# Controller_Sheet.net
KiCad netlist of a schematic drawn in Altium Designer
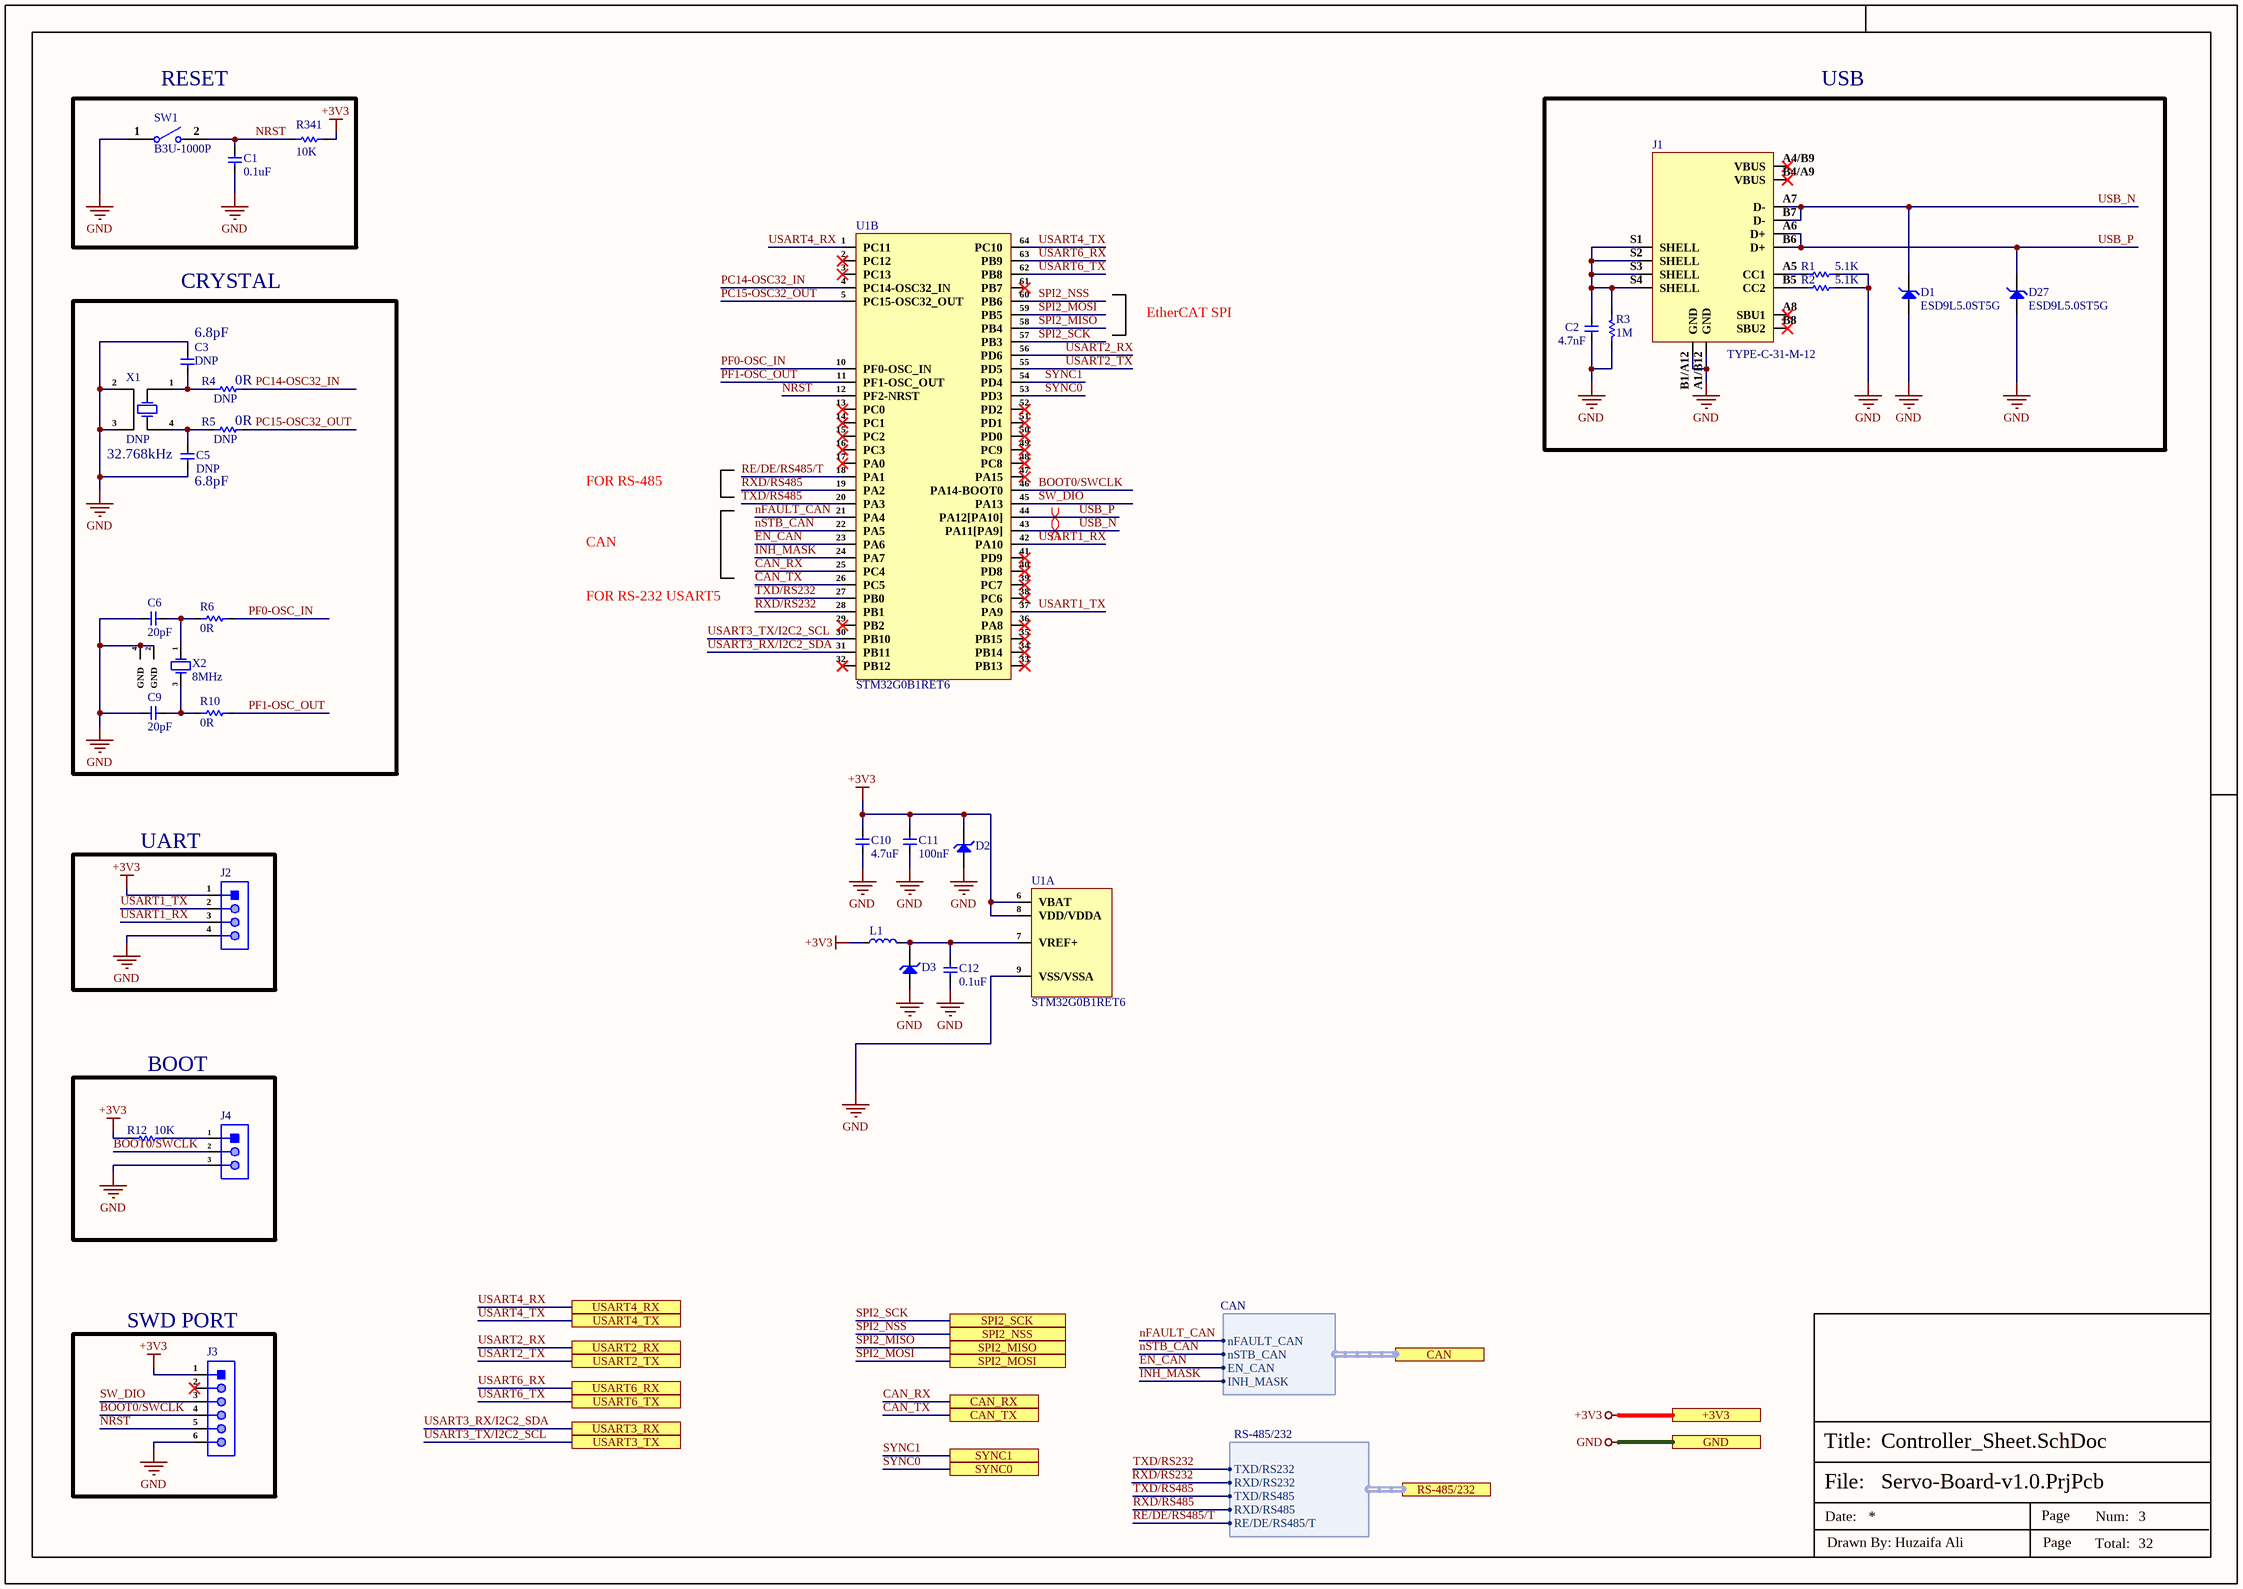
[diagram p0: Controller_Sheet.SchDoc]

(export (version "E")
  (design (tool "Eeschema 10.0.6"))
  (components
    (comp (ref "C1")
      (value "0.1uF")
      (footprint "Cap-0402")
      (description "CAP CER 0.1UF 16V X7R 0402")
      (fields
        (field (name "MANUFACTURER") "Yageo")
        (field (name "MANUFACTURER PART NUMBER") "CC0402JRX7R7BB104")
      )
      (libsource (lib "eSpark Libraries") (part "CC0402JRX7R7BB104"))
    )
    (comp (ref "C2")
      (value "4.7nF")
      (footprint "Cap-0603")
      (description "CAP CER 4700PF 50V C0G/NPO 0603")
      (fields
        (field (name "MANUFACTURER") "Yageo")
        (field (name "MANUFACTURER PART NUMBER") "CC0603JRNPO9BN472")
      )
      (libsource (lib "eSpark_centralized_Library(2022)") (part "CC0603JRNPO9BN472"))
    )
    (comp (ref "C3")
      (value "DNP")
      (footprint "Cap-0402")
      (description "CAP CER 6.8PF 50V C0G/NPO 0402")
      (fields
        (field (name "MANUFACTURER") "Yageo")
        (field (name "MANUFACTURER PART NUMBER") "CC0402CRNPO9BN6R8")
      )
      (libsource (lib "eSpark Libraries") (part "CC0402CRNPO9BN6R8"))
    )
    (comp (ref "C5")
      (value "DNP")
      (footprint "Cap-0402")
      (description "CAP CER 6.8PF 50V C0G/NPO 0402")
      (fields
        (field (name "MANUFACTURER") "Yageo")
        (field (name "MANUFACTURER PART NUMBER") "CC0402CRNPO9BN6R8")
      )
      (libsource (lib "eSpark Libraries") (part "CC0402CRNPO9BN6R8"))
    )
    (comp (ref "C6")
      (value "20pF")
      (footprint "Cap-0402")
      (description "CAP CER 20PF 50V C0G/NPO 0402")
      (fields (field (name "LCSC PART NUMBER") "C107000") (field (name "MANUFACTURER") "Yageo"))
      (libsource (lib "eSpark Libraries") (part "CC0402JRNPO9BN200"))
    )
    (comp (ref "C9")
      (value "20pF")
      (footprint "Cap-0402")
      (description "CAP CER 20PF 50V C0G/NPO 0402")
      (fields (field (name "LCSC PART NUMBER") "C107000") (field (name "MANUFACTURER") "Yageo"))
      (libsource (lib "eSpark Libraries") (part "CC0402JRNPO9BN200"))
    )
    (comp (ref "C10")
      (value "4.7uF")
      (footprint "Cap-0402")
      (description "CAP CER 4.7UF 10V X5R 0402")
      (fields
        (field (name "MANUFACTURER") "Yageo")
        (field (name "MANUFACTURER PART NUMBER") "CC0402KRX5R6BB475")
      )
      (libsource (lib "eSpark Libraries") (part "CC0402KRX5R6BB475"))
    )
    (comp (ref "C11")
      (value "100nF")
      (footprint "cap-0402")
      (description "CAP CER 0.1UF 50V X7R 0402")
      (fields
        (field (name "MANUFACTURER") "TDK")
        (field (name "MANUFACTURER PART NUMBER") "C1005X7R1H104KT000F")
      )
      (libsource (lib "eSpark Libraries") (part "C1005X7R1H104KT000F"))
    )
    (comp (ref "C12")
      (value "0.1uF")
      (footprint "Cap-0402")
      (description "CAP CER 0.1UF 16V X7R 0402")
      (fields
        (field (name "MANUFACTURER") "Yageo")
        (field (name "MANUFACTURER PART NUMBER") "CC0402JRX7R7BB104")
      )
      (libsource (lib "eSpark Libraries") (part "CC0402JRX7R7BB104"))
    )
    (comp (ref "D1")
      (value "ESD9L5.0ST5G")
      (footprint "SOD-923.")
      (description "TVS DIODE 5V 9.8V SOD923")
      (fields (field (name "MANUFACTURER") "ON Semiconductor") (field (name "LCSC PART NUMBER") "C82326"))
      (libsource (lib "eSpark Libraries") (part "ESD9L5.0ST5G"))
    )
    (comp (ref "D2")
      (value "AZ3003-01G")
      (footprint "SOD-123")
      (description "TVS SURGE PROTECTOR 1-CH 3.3V")
      (fields (field (name "MANUFACTURER") "Amazing"))
      (libsource (lib "eSpark Libraries") (part "AZ3003-01G"))
    )
    (comp (ref "D3")
      (value "AZ3003-01G")
      (footprint "SOD-123")
      (description "TVS SURGE PROTECTOR 1-CH 3.3V")
      (fields (field (name "MANUFACTURER") "Amazing"))
      (libsource (lib "eSpark Libraries") (part "AZ3003-01G"))
    )
    (comp (ref "D27")
      (value "ESD9L5.0ST5G")
      (footprint "SOD-923.")
      (description "TVS DIODE 5V 9.8V SOD923")
      (fields (field (name "MANUFACTURER") "ON Semiconductor") (field (name "LCSC PART NUMBER") "C82326"))
      (libsource (lib "eSpark Libraries") (part "ESD9L5.0ST5G"))
    )
    (comp (ref "J1")
      (value "TYPE-C-31-M-12")
      (footprint "TYPE-C-31-M-12_")
      (description "5A 1 16P Female Type-C SMD USB Connectors ROHS")
      (fields
        (field (name "MANUFACTURER") "Korean Hroparts Elec")
        (field (name "LCSC PART NUMBER") "C165948")
      )
      (libsource (lib "eSpark Libraries") (part "TYPE-C-31-M-12"))
    )
    (comp (ref "J2")
      (value "X6511WV-04H-C60D30")
      (footprint "HDR1X4_")
      (fields (field (name "MANUFACTURER") "XKB") (field (name "LCSC PART NUMBER") "C706876"))
      (libsource (lib "eSpark Libraries") (part "X6511WV-04H-C60D30"))
    )
    (comp (ref "J3")
      (value "X6511WV-06H-C60D30")
      (footprint "HDR1X6_")
      (fields (field (name "MANUFACTURER") "XKB") (field (name "LCSC PART NUMBER") "C706878"))
      (libsource (lib "eSpark Libraries") (part "X6511WV-06H-C60D30"))
    )
    (comp (ref "J4")
      (value "68000-103HLF")
      (footprint "HDR1X3_")
      (description "CONN HEADER VERT 3POS 2.54MM")
      (fields (field (name "LCSC PART NUMBER") "C168677"))
      (libsource (lib "eSpark Libraries") (part "68000-103HLF"))
    )
    (comp (ref "L1")
      (value "BLM15AG601SN1D")
      (footprint "IND-0402")
      (description "FERRITE BEAD 600 OHM 0402 1LN")
      (fields (field (name "MANUFACTURER") "Murata") (field (name "TOLERANCE") "25%"))
      (libsource (lib "eSpark Libraries") (part "BLM15AG601SN1D"))
    )
    (comp (ref "R1")
      (value "5.1K")
      (footprint "Res-0402")
      (description "RES 5.1K OHM 1% 1/16W 0402")
      (fields
        (field (name "MANUFACTURER") "Yageo")
        (field (name "MANUFACTURER PART NUMBER") "RC0402FR-075K1L")
      )
      (libsource (lib "eSpark Libraries") (part "RC0402FR-075K1L"))
    )
    (comp (ref "R2")
      (value "5.1K")
      (footprint "Res-0402")
      (description "RES 5.1K OHM 1% 1/16W 0402")
      (fields
        (field (name "MANUFACTURER") "Yageo")
        (field (name "MANUFACTURER PART NUMBER") "RC0402FR-075K1L")
      )
      (libsource (lib "eSpark Libraries") (part "RC0402FR-075K1L"))
    )
    (comp (ref "R3")
      (value "1M")
      (footprint "Res-0402")
      (description "RES SMD 1M OHM 5% 1/16W 0402")
      (fields
        (field (name "MANUFACTURER") "Yageo")
        (field (name "MANUFACTURER PART NUMBER") "AF0402JR-071ML")
      )
      (libsource (lib "eSpark_centralized_Library(2022)") (part "AF0402JR-071ML"))
    )
    (comp (ref "R4")
      (value "DNP")
      (footprint "Res-0603")
      (description "RES 0 OHM JUMPER 1/10W 0603")
      (fields
        (field (name "MANUFACTURER") "Yageo")
        (field (name "MANUFACTURER PART NUMBER") "RC0603JR-070RL")
      )
      (libsource (lib "eSpark Libraries") (part "RC0603JR-070RL"))
    )
    (comp (ref "R5")
      (value "DNP")
      (footprint "Res-0603")
      (description "RES 0 OHM JUMPER 1/10W 0603")
      (fields
        (field (name "MANUFACTURER") "Yageo")
        (field (name "MANUFACTURER PART NUMBER") "RC0603JR-070RL")
      )
      (libsource (lib "eSpark Libraries") (part "RC0603JR-070RL"))
    )
    (comp (ref "R6")
      (value "0R")
      (footprint "Res-0603")
      (description "RES 0 OHM JUMPER 1/10W 0603")
      (fields
        (field (name "MANUFACTURER") "Yageo")
        (field (name "MANUFACTURER PART NUMBER") "RC0603JR-070RL")
      )
      (libsource (lib "eSpark Libraries") (part "RC0603JR-070RL"))
    )
    (comp (ref "R10")
      (value "0R")
      (footprint "Res-0603")
      (description "RES 0 OHM JUMPER 1/10W 0603")
      (fields
        (field (name "MANUFACTURER") "Yageo")
        (field (name "MANUFACTURER PART NUMBER") "RC0603JR-070RL")
      )
      (libsource (lib "eSpark Libraries") (part "RC0603JR-070RL"))
    )
    (comp (ref "R12")
      (value "10K")
      (footprint "Res-0402")
      (description "RES 10K OHM 1% 1/16W 0402")
      (fields
        (field (name "MANUFACTURER") "Yageo")
        (field (name "MANUFACTURER PART NUMBER") "RC0402FR-0710KL")
      )
      (libsource (lib "eSpark Libraries") (part "RC0402FR-0710KL"))
    )
    (comp (ref "R341")
      (value "10K")
      (footprint "Res-0402")
      (description "RES 10K OHM 1% 1/16W 0402")
      (fields
        (field (name "MANUFACTURER") "Yageo")
        (field (name "MANUFACTURER PART NUMBER") "RC0402FR-0710KL")
      )
      (libsource (lib "eSpark Libraries") (part "RC0402FR-0710KL"))
    )
    (comp (ref "SW1")
      (value "B3U-1000P")
      (footprint "B3U-1000P")
      (description "SWITCH TACTILE SPST-NO 0.05A 12V")
      (fields (field (name "MANUFACTURER") "Omron") (field (name "LCSC PART NUMBER") "C231329"))
      (libsource (lib "eSpark Libraries") (part "B3U-1000P"))
    )
    (comp (ref "U1")
      (value "STM32G0B1RET6")
      (footprint "LQFP-64(10x10)")
      (description "IC MCU 32BIT 512KB FLASH 64LQFP")
      (fields (field (name "MANUFACTURER") "STMicroelectronics") (field (name "LCSC PART NUMBER") "C2829307"))
      (libsource (lib "eSpark Libraries") (part "STM32G0B1RET6"))
    )
    (comp (ref "X1")
      (value "DNP")
      (footprint "MC-306")
      (description "32.768kHz 12.5pF ±20ppm MC-306 Crystals ROHS")
      (fields
        (field (name "MANUFACTURER") "Seiko Epson")
        (field (name "MANUFACTURER PART NUMBER") "MC-306 32.7680K-A0:ROHS")
      )
      (libsource (lib "eSpark Libraries") (part "MC-306 32.7680K-A0{colon}ROHS"))
    )
    (comp (ref "X2")
      (value "8MHz")
      (footprint "5TJ480000XYLBC_")
      (description "8MHz 18pF ±10ppm SMD5032-4P Crystals ROHS")
      (fields (field (name "MANUFACTURER") "JYJE") (field (name "MANUFACTURER PART NUMBER") "5TJ480000XYLBC"))
      (libsource (lib "eSpark Libraries") (part "5TJ480000XYLBC"))
    )
  )
  (nets
    (net (code "3") (name "+3V3") (class "Default")
      (node (ref "C10") (pin "2") (pinfunction "2_2") (pintype "passive"))
      (node (ref "C11") (pin "2") (pinfunction "2_2") (pintype "passive"))
      (node (ref "D2") (pin "2") (pinfunction "K_2") (pintype "passive"))
      (node (ref "J2") (pin "1") (pinfunction "1_1") (pintype "passive"))
      (node (ref "J3") (pin "1") (pinfunction "1_1") (pintype "passive"))
      (node (ref "L1") (pin "1") (pinfunction "1_1") (pintype "passive"))
      (node (ref "R12") (pin "2") (pinfunction "2_2") (pintype "passive"))
      (node (ref "R341") (pin "2") (pinfunction "2_2") (pintype "passive"))
      (node (ref "U1") (pin "6") (pinfunction "VBAT_6") (pintype "passive"))
      (node (ref "U1") (pin "8") (pinfunction "VDD/VDDA_8") (pintype "passive"))
    )
    (net (code "4") (name "/BOOT0{slash}SWCLK") (class "Default")
      (node (ref "J3") (pin "4") (pinfunction "4_4") (pintype "passive"))
      (node (ref "J4") (pin "2") (pinfunction "2_2") (pintype "passive"))
      (node (ref "U1") (pin "46") (pinfunction "PA14-BOOT0_46") (pintype "passive"))
    )
    (net (code "5") (name "/CAN_RX") (class "Default")
      (node (ref "U1") (pin "25") (pinfunction "PC4_25") (pintype "passive"))
    )
    (net (code "6") (name "/CAN_TX") (class "Default")
      (node (ref "U1") (pin "26") (pinfunction "PC5_26") (pintype "passive"))
    )
    (net (code "7") (name "/EN_CAN") (class "Default")
      (node (ref "U1") (pin "23") (pinfunction "PA6_23") (pintype "passive"))
    )
    (net (code "8") (name "/INH_MASK") (class "Default")
      (node (ref "U1") (pin "24") (pinfunction "PA7_24") (pintype "passive"))
    )
    (net (code "9") (name "/NRST") (class "Default")
      (node (ref "C1") (pin "2") (pinfunction "2_2") (pintype "passive"))
      (node (ref "J3") (pin "5") (pinfunction "5_5") (pintype "passive"))
      (node (ref "R341") (pin "1") (pinfunction "1_1") (pintype "passive"))
      (node (ref "SW1") (pin "2") (pinfunction "2_2") (pintype "passive"))
      (node (ref "U1") (pin "12") (pinfunction "PF2-NRST_12") (pintype "passive"))
    )
    (net (code "10") (name "/PC14-OSC32_IN") (class "Default")
      (node (ref "R4") (pin "2") (pinfunction "2_2") (pintype "passive"))
      (node (ref "U1") (pin "4") (pinfunction "PC14-OSC32_IN_4") (pintype "passive"))
    )
    (net (code "11") (name "/PC15-OSC32_OUT") (class "Default")
      (node (ref "R5") (pin "2") (pinfunction "2_2") (pintype "passive"))
      (node (ref "U1") (pin "5") (pinfunction "PC15-OSC32_OUT_5") (pintype "passive"))
    )
    (net (code "12") (name "/PF0-OSC_IN") (class "Default")
      (node (ref "R6") (pin "2") (pinfunction "2_2") (pintype "passive"))
      (node (ref "U1") (pin "10") (pinfunction "PF0-OSC_IN_10") (pintype "passive"))
    )
    (net (code "13") (name "/PF1-OSC_OUT") (class "Default")
      (node (ref "R10") (pin "2") (pinfunction "2_2") (pintype "passive"))
      (node (ref "U1") (pin "11") (pinfunction "PF1-OSC_OUT_11") (pintype "passive"))
    )
    (net (code "14") (name "/RE{slash}DE{slash}RS485{slash}T") (class "Default")
      (node (ref "U1") (pin "18") (pinfunction "PA1_18") (pintype "passive"))
    )
    (net (code "15") (name "/RXD{slash}RS232") (class "Default")
      (node (ref "U1") (pin "28") (pinfunction "PB1_28") (pintype "passive"))
    )
    (net (code "16") (name "/RXD{slash}RS485") (class "Default")
      (node (ref "U1") (pin "19") (pinfunction "PA2_19") (pintype "passive"))
    )
    (net (code "17") (name "/SPI2_MISO") (class "Default")
      (node (ref "U1") (pin "58") (pinfunction "PB4_58") (pintype "passive"))
    )
    (net (code "18") (name "/SPI2_MOSI") (class "Default")
      (node (ref "U1") (pin "59") (pinfunction "PB5_59") (pintype "passive"))
    )
    (net (code "19") (name "/SPI2_NSS") (class "Default")
      (node (ref "U1") (pin "60") (pinfunction "PB6_60") (pintype "passive"))
    )
    (net (code "20") (name "/SPI2_SCK") (class "Default")
      (node (ref "U1") (pin "57") (pinfunction "PB3_57") (pintype "passive"))
    )
    (net (code "21") (name "/SW_DIO") (class "Default")
      (node (ref "J3") (pin "3") (pinfunction "3_3") (pintype "passive"))
      (node (ref "U1") (pin "45") (pinfunction "PA13_45") (pintype "passive"))
    )
    (net (code "22") (name "/SYNC0") (class "Default")
      (node (ref "U1") (pin "53") (pinfunction "PD3_53") (pintype "passive"))
    )
    (net (code "23") (name "/SYNC1") (class "Default")
      (node (ref "U1") (pin "54") (pinfunction "PD4_54") (pintype "passive"))
    )
    (net (code "24") (name "/TXD{slash}RS232") (class "Default")
      (node (ref "U1") (pin "27") (pinfunction "PB0_27") (pintype "passive"))
    )
    (net (code "25") (name "/TXD{slash}RS485") (class "Default")
      (node (ref "U1") (pin "20") (pinfunction "PA3_20") (pintype "passive"))
    )
    (net (code "26") (name "/USART1_RX") (class "Default")
      (node (ref "J2") (pin "3") (pinfunction "3_3") (pintype "passive"))
      (node (ref "U1") (pin "42") (pinfunction "PA10_42") (pintype "passive"))
    )
    (net (code "27") (name "/USART1_TX") (class "Default")
      (node (ref "J2") (pin "2") (pinfunction "2_2") (pintype "passive"))
      (node (ref "U1") (pin "37") (pinfunction "PA9_37") (pintype "passive"))
    )
    (net (code "28") (name "/USART2_RX") (class "Default")
      (node (ref "U1") (pin "56") (pinfunction "PD6_56") (pintype "passive"))
    )
    (net (code "29") (name "/USART2_TX") (class "Default")
      (node (ref "U1") (pin "55") (pinfunction "PD5_55") (pintype "passive"))
    )
    (net (code "30") (name "/USART3_RX{slash}I2C2_SDA") (class "Default")
      (node (ref "U1") (pin "31") (pinfunction "PB11_31") (pintype "passive"))
    )
    (net (code "31") (name "/USART3_TX{slash}I2C2_SCL") (class "Default")
      (node (ref "U1") (pin "30") (pinfunction "PB10_30") (pintype "passive"))
    )
    (net (code "32") (name "/USART4_RX") (class "Default")
      (node (ref "U1") (pin "1") (pinfunction "PC11_1") (pintype "passive"))
    )
    (net (code "33") (name "/USART4_TX") (class "Default")
      (node (ref "U1") (pin "64") (pinfunction "PC10_64") (pintype "passive"))
    )
    (net (code "34") (name "/USART6_RX") (class "Default")
      (node (ref "U1") (pin "63") (pinfunction "PB9_63") (pintype "passive"))
    )
    (net (code "35") (name "/USART6_TX") (class "Default")
      (node (ref "U1") (pin "62") (pinfunction "PB8_62") (pintype "passive"))
    )
    (net (code "36") (name "/USB_N") (class "Default")
      (node (ref "D1") (pin "1") (pinfunction "K_1") (pintype "passive"))
      (node (ref "J1") (pin "A7") (pinfunction "D-_A7") (pintype "passive"))
      (node (ref "J1") (pin "B7") (pinfunction "D-_B7") (pintype "passive"))
      (node (ref "U1") (pin "43") (pinfunction "PA11[PA9]_43") (pintype "passive"))
    )
    (net (code "37") (name "/USB_P") (class "Default")
      (node (ref "D27") (pin "1") (pinfunction "K_1") (pintype "passive"))
      (node (ref "J1") (pin "A6") (pinfunction "D+_A6") (pintype "passive"))
      (node (ref "J1") (pin "B6") (pinfunction "D+_B6") (pintype "passive"))
      (node (ref "U1") (pin "44") (pinfunction "PA12[PA10]_44") (pintype "passive"))
    )
    (net (code "38") (name "/nFAULT_CAN") (class "Default")
      (node (ref "U1") (pin "21") (pinfunction "PA4_21") (pintype "passive"))
    )
    (net (code "39") (name "/nSTB_CAN") (class "Default")
      (node (ref "U1") (pin "22") (pinfunction "PA5_22") (pintype "passive"))
    )
    (net (code "42") (name "GND") (class "Default")
      (node (ref "C1") (pin "1") (pinfunction "1_1") (pintype "passive"))
      (node (ref "C10") (pin "1") (pinfunction "1_1") (pintype "passive"))
      (node (ref "C11") (pin "1") (pinfunction "1_1") (pintype "passive"))
      (node (ref "C12") (pin "1") (pinfunction "1_1") (pintype "passive"))
      (node (ref "C2") (pin "1") (pinfunction "1_1") (pintype "passive"))
      (node (ref "C3") (pin "1") (pinfunction "1_1") (pintype "passive"))
      (node (ref "C5") (pin "2") (pinfunction "2_2") (pintype "passive"))
      (node (ref "C6") (pin "1") (pinfunction "1_1") (pintype "passive"))
      (node (ref "C9") (pin "1") (pinfunction "1_1") (pintype "passive"))
      (node (ref "D1") (pin "2") (pinfunction "A_2") (pintype "passive"))
      (node (ref "D2") (pin "1") (pinfunction "A_1") (pintype "passive"))
      (node (ref "D27") (pin "2") (pinfunction "A_2") (pintype "passive"))
      (node (ref "D3") (pin "1") (pinfunction "A_1") (pintype "passive"))
      (node (ref "J1") (pin "A1/B12") (pinfunction "GND_A1/B12") (pintype "power_in"))
      (node (ref "J1") (pin "B1/A12") (pinfunction "GND_B1/A12") (pintype "power_in"))
      (node (ref "J2") (pin "4") (pinfunction "4_4") (pintype "passive"))
      (node (ref "J3") (pin "6") (pinfunction "6_6") (pintype "passive"))
      (node (ref "J4") (pin "3") (pinfunction "3_3") (pintype "passive"))
      (node (ref "R1") (pin "2") (pinfunction "2_2") (pintype "passive"))
      (node (ref "R2") (pin "2") (pinfunction "2_2") (pintype "passive"))
      (node (ref "R3") (pin "2") (pinfunction "2_2") (pintype "passive"))
      (node (ref "SW1") (pin "1") (pinfunction "1_1") (pintype "passive"))
      (node (ref "U1") (pin "9") (pinfunction "VSS/VSSA_9") (pintype "passive"))
      (node (ref "X1") (pin "2") (pinfunction "2_2") (pintype "passive"))
      (node (ref "X1") (pin "3") (pinfunction "3_3") (pintype "passive"))
      (node (ref "X2") (pin "2") (pinfunction "GND_2") (pintype "passive"))
      (node (ref "X2") (pin "4") (pinfunction "GND_4") (pintype "passive"))
    )
    (net (code "43") (name "Net-(C2-Pad2)") (class "Default")
      (node (ref "C2") (pin "2") (pinfunction "2_2") (pintype "passive"))
      (node (ref "J1") (pin "S1") (pinfunction "SHELL_S1") (pintype "passive"))
      (node (ref "J1") (pin "S2") (pinfunction "SHELL_S2") (pintype "passive"))
      (node (ref "J1") (pin "S3") (pinfunction "SHELL_S3") (pintype "passive"))
      (node (ref "J1") (pin "S4") (pinfunction "SHELL_S4") (pintype "passive"))
      (node (ref "R3") (pin "1") (pinfunction "1_1") (pintype "passive"))
    )
    (net (code "44") (name "Net-(D3-K)") (class "Default")
      (node (ref "C12") (pin "2") (pinfunction "2_2") (pintype "passive"))
      (node (ref "D3") (pin "2") (pinfunction "K_2") (pintype "passive"))
      (node (ref "L1") (pin "2") (pinfunction "2_2") (pintype "passive"))
      (node (ref "U1") (pin "7") (pinfunction "VREF+_7") (pintype "passive"))
    )
    (net (code "45") (name "Net-(J1-CC1)") (class "Default")
      (node (ref "J1") (pin "A5") (pinfunction "CC1_A5") (pintype "passive"))
      (node (ref "R1") (pin "1") (pinfunction "1_1") (pintype "passive"))
    )
    (net (code "46") (name "Net-(J1-CC2)") (class "Default")
      (node (ref "J1") (pin "B5") (pinfunction "CC2_B5") (pintype "passive"))
      (node (ref "R2") (pin "1") (pinfunction "1_1") (pintype "passive"))
    )
    (net (code "47") (name "Net-(J4-Pad1)") (class "Default")
      (node (ref "J4") (pin "1") (pinfunction "1_1") (pintype "passive"))
      (node (ref "R12") (pin "1") (pinfunction "1_1") (pintype "passive"))
    )
    (net (code "48") (name "Net-(X1-OSC1)") (class "Default")
      (node (ref "C3") (pin "2") (pinfunction "2_2") (pintype "passive"))
      (node (ref "R4") (pin "1") (pinfunction "1_1") (pintype "passive"))
      (node (ref "X1") (pin "1") (pinfunction "OSC1_1") (pintype "passive"))
    )
    (net (code "49") (name "Net-(X1-OSC2)") (class "Default")
      (node (ref "C5") (pin "1") (pinfunction "1_1") (pintype "passive"))
      (node (ref "R5") (pin "1") (pinfunction "1_1") (pintype "passive"))
      (node (ref "X1") (pin "4") (pinfunction "OSC2_4") (pintype "passive"))
    )
    (net (code "50") (name "Net-(X2-OSC1)") (class "Default")
      (node (ref "C6") (pin "2") (pinfunction "2_2") (pintype "passive"))
      (node (ref "R6") (pin "1") (pinfunction "1_1") (pintype "passive"))
      (node (ref "X2") (pin "1") (pinfunction "OSC1_1") (pintype "passive"))
    )
    (net (code "51") (name "Net-(X2-OSC2)") (class "Default")
      (node (ref "C9") (pin "2") (pinfunction "2_2") (pintype "passive"))
      (node (ref "R10") (pin "1") (pinfunction "1_1") (pintype "passive"))
      (node (ref "X2") (pin "3") (pinfunction "OSC2_3") (pintype "passive"))
    )
    (net (code "52") (name "unconnected-(J1-SBU1-PadA8)") (class "Default")
      (node (ref "J1") (pin "A8") (pinfunction "SBU1_A8") (pintype "passive+no_connect"))
    )
    (net (code "53") (name "unconnected-(J1-SBU2-PadB8)") (class "Default")
      (node (ref "J1") (pin "B8") (pinfunction "SBU2_B8") (pintype "passive+no_connect"))
    )
    (net (code "54") (name "unconnected-(J1-VBUS-PadA4{slash}B9)") (class "Default")
      (node (ref "J1") (pin "A4/B9") (pinfunction "VBUS_A4/B9") (pintype "power_in+no_connect"))
    )
    (net (code "55") (name "unconnected-(J1-VBUS-PadB4{slash}A9)") (class "Default")
      (node (ref "J1") (pin "B4/A9") (pinfunction "VBUS_B4/A9") (pintype "power_in+no_connect"))
    )
    (net (code "56") (name "unconnected-(J3-Pad2)") (class "Default")
      (node (ref "J3") (pin "2") (pinfunction "2_2") (pintype "passive+no_connect"))
    )
    (net (code "57") (name "unconnected-(U1B-PA0-Pad17)") (class "Default")
      (node (ref "U1") (pin "17") (pinfunction "PA0_17") (pintype "passive+no_connect"))
    )
    (net (code "58") (name "unconnected-(U1B-PA8-Pad36)") (class "Default")
      (node (ref "U1") (pin "36") (pinfunction "PA8_36") (pintype "passive+no_connect"))
    )
    (net (code "59") (name "unconnected-(U1B-PA15-Pad47)") (class "Default")
      (node (ref "U1") (pin "47") (pinfunction "PA15_47") (pintype "passive+no_connect"))
    )
    (net (code "60") (name "unconnected-(U1B-PB2-Pad29)") (class "Default")
      (node (ref "U1") (pin "29") (pinfunction "PB2_29") (pintype "passive+no_connect"))
    )
    (net (code "61") (name "unconnected-(U1B-PB7-Pad61)") (class "Default")
      (node (ref "U1") (pin "61") (pinfunction "PB7_61") (pintype "passive+no_connect"))
    )
    (net (code "62") (name "unconnected-(U1B-PB12-Pad32)") (class "Default")
      (node (ref "U1") (pin "32") (pinfunction "PB12_32") (pintype "passive+no_connect"))
    )
    (net (code "63") (name "unconnected-(U1B-PB13-Pad33)") (class "Default")
      (node (ref "U1") (pin "33") (pinfunction "PB13_33") (pintype "passive+no_connect"))
    )
    (net (code "64") (name "unconnected-(U1B-PB14-Pad34)") (class "Default")
      (node (ref "U1") (pin "34") (pinfunction "PB14_34") (pintype "passive+no_connect"))
    )
    (net (code "65") (name "unconnected-(U1B-PB15-Pad35)") (class "Default")
      (node (ref "U1") (pin "35") (pinfunction "PB15_35") (pintype "passive+no_connect"))
    )
    (net (code "66") (name "unconnected-(U1B-PC0-Pad13)") (class "Default")
      (node (ref "U1") (pin "13") (pinfunction "PC0_13") (pintype "passive+no_connect"))
    )
    (net (code "67") (name "unconnected-(U1B-PC1-Pad14)") (class "Default")
      (node (ref "U1") (pin "14") (pinfunction "PC1_14") (pintype "passive+no_connect"))
    )
    (net (code "68") (name "unconnected-(U1B-PC2-Pad15)") (class "Default")
      (node (ref "U1") (pin "15") (pinfunction "PC2_15") (pintype "passive+no_connect"))
    )
    (net (code "69") (name "unconnected-(U1B-PC3-Pad16)") (class "Default")
      (node (ref "U1") (pin "16") (pinfunction "PC3_16") (pintype "passive+no_connect"))
    )
    (net (code "70") (name "unconnected-(U1B-PC6-Pad38)") (class "Default")
      (node (ref "U1") (pin "38") (pinfunction "PC6_38") (pintype "passive+no_connect"))
    )
    (net (code "71") (name "unconnected-(U1B-PC7-Pad39)") (class "Default")
      (node (ref "U1") (pin "39") (pinfunction "PC7_39") (pintype "passive+no_connect"))
    )
    (net (code "72") (name "unconnected-(U1B-PC8-Pad48)") (class "Default")
      (node (ref "U1") (pin "48") (pinfunction "PC8_48") (pintype "passive+no_connect"))
    )
    (net (code "73") (name "unconnected-(U1B-PC9-Pad49)") (class "Default")
      (node (ref "U1") (pin "49") (pinfunction "PC9_49") (pintype "passive+no_connect"))
    )
    (net (code "74") (name "unconnected-(U1B-PC12-Pad2)") (class "Default")
      (node (ref "U1") (pin "2") (pinfunction "PC12_2") (pintype "passive+no_connect"))
    )
    (net (code "75") (name "unconnected-(U1B-PC13-Pad3)") (class "Default")
      (node (ref "U1") (pin "3") (pinfunction "PC13_3") (pintype "passive+no_connect"))
    )
    (net (code "76") (name "unconnected-(U1B-PD0-Pad50)") (class "Default")
      (node (ref "U1") (pin "50") (pinfunction "PD0_50") (pintype "passive+no_connect"))
    )
    (net (code "77") (name "unconnected-(U1B-PD1-Pad51)") (class "Default")
      (node (ref "U1") (pin "51") (pinfunction "PD1_51") (pintype "passive+no_connect"))
    )
    (net (code "78") (name "unconnected-(U1B-PD2-Pad52)") (class "Default")
      (node (ref "U1") (pin "52") (pinfunction "PD2_52") (pintype "passive+no_connect"))
    )
    (net (code "79") (name "unconnected-(U1B-PD8-Pad40)") (class "Default")
      (node (ref "U1") (pin "40") (pinfunction "PD8_40") (pintype "passive+no_connect"))
    )
    (net (code "80") (name "unconnected-(U1B-PD9-Pad41)") (class "Default")
      (node (ref "U1") (pin "41") (pinfunction "PD9_41") (pintype "passive+no_connect"))
    )
  )
)
